# power.net
KiCad netlist of a schematic drawn in Altium Designer
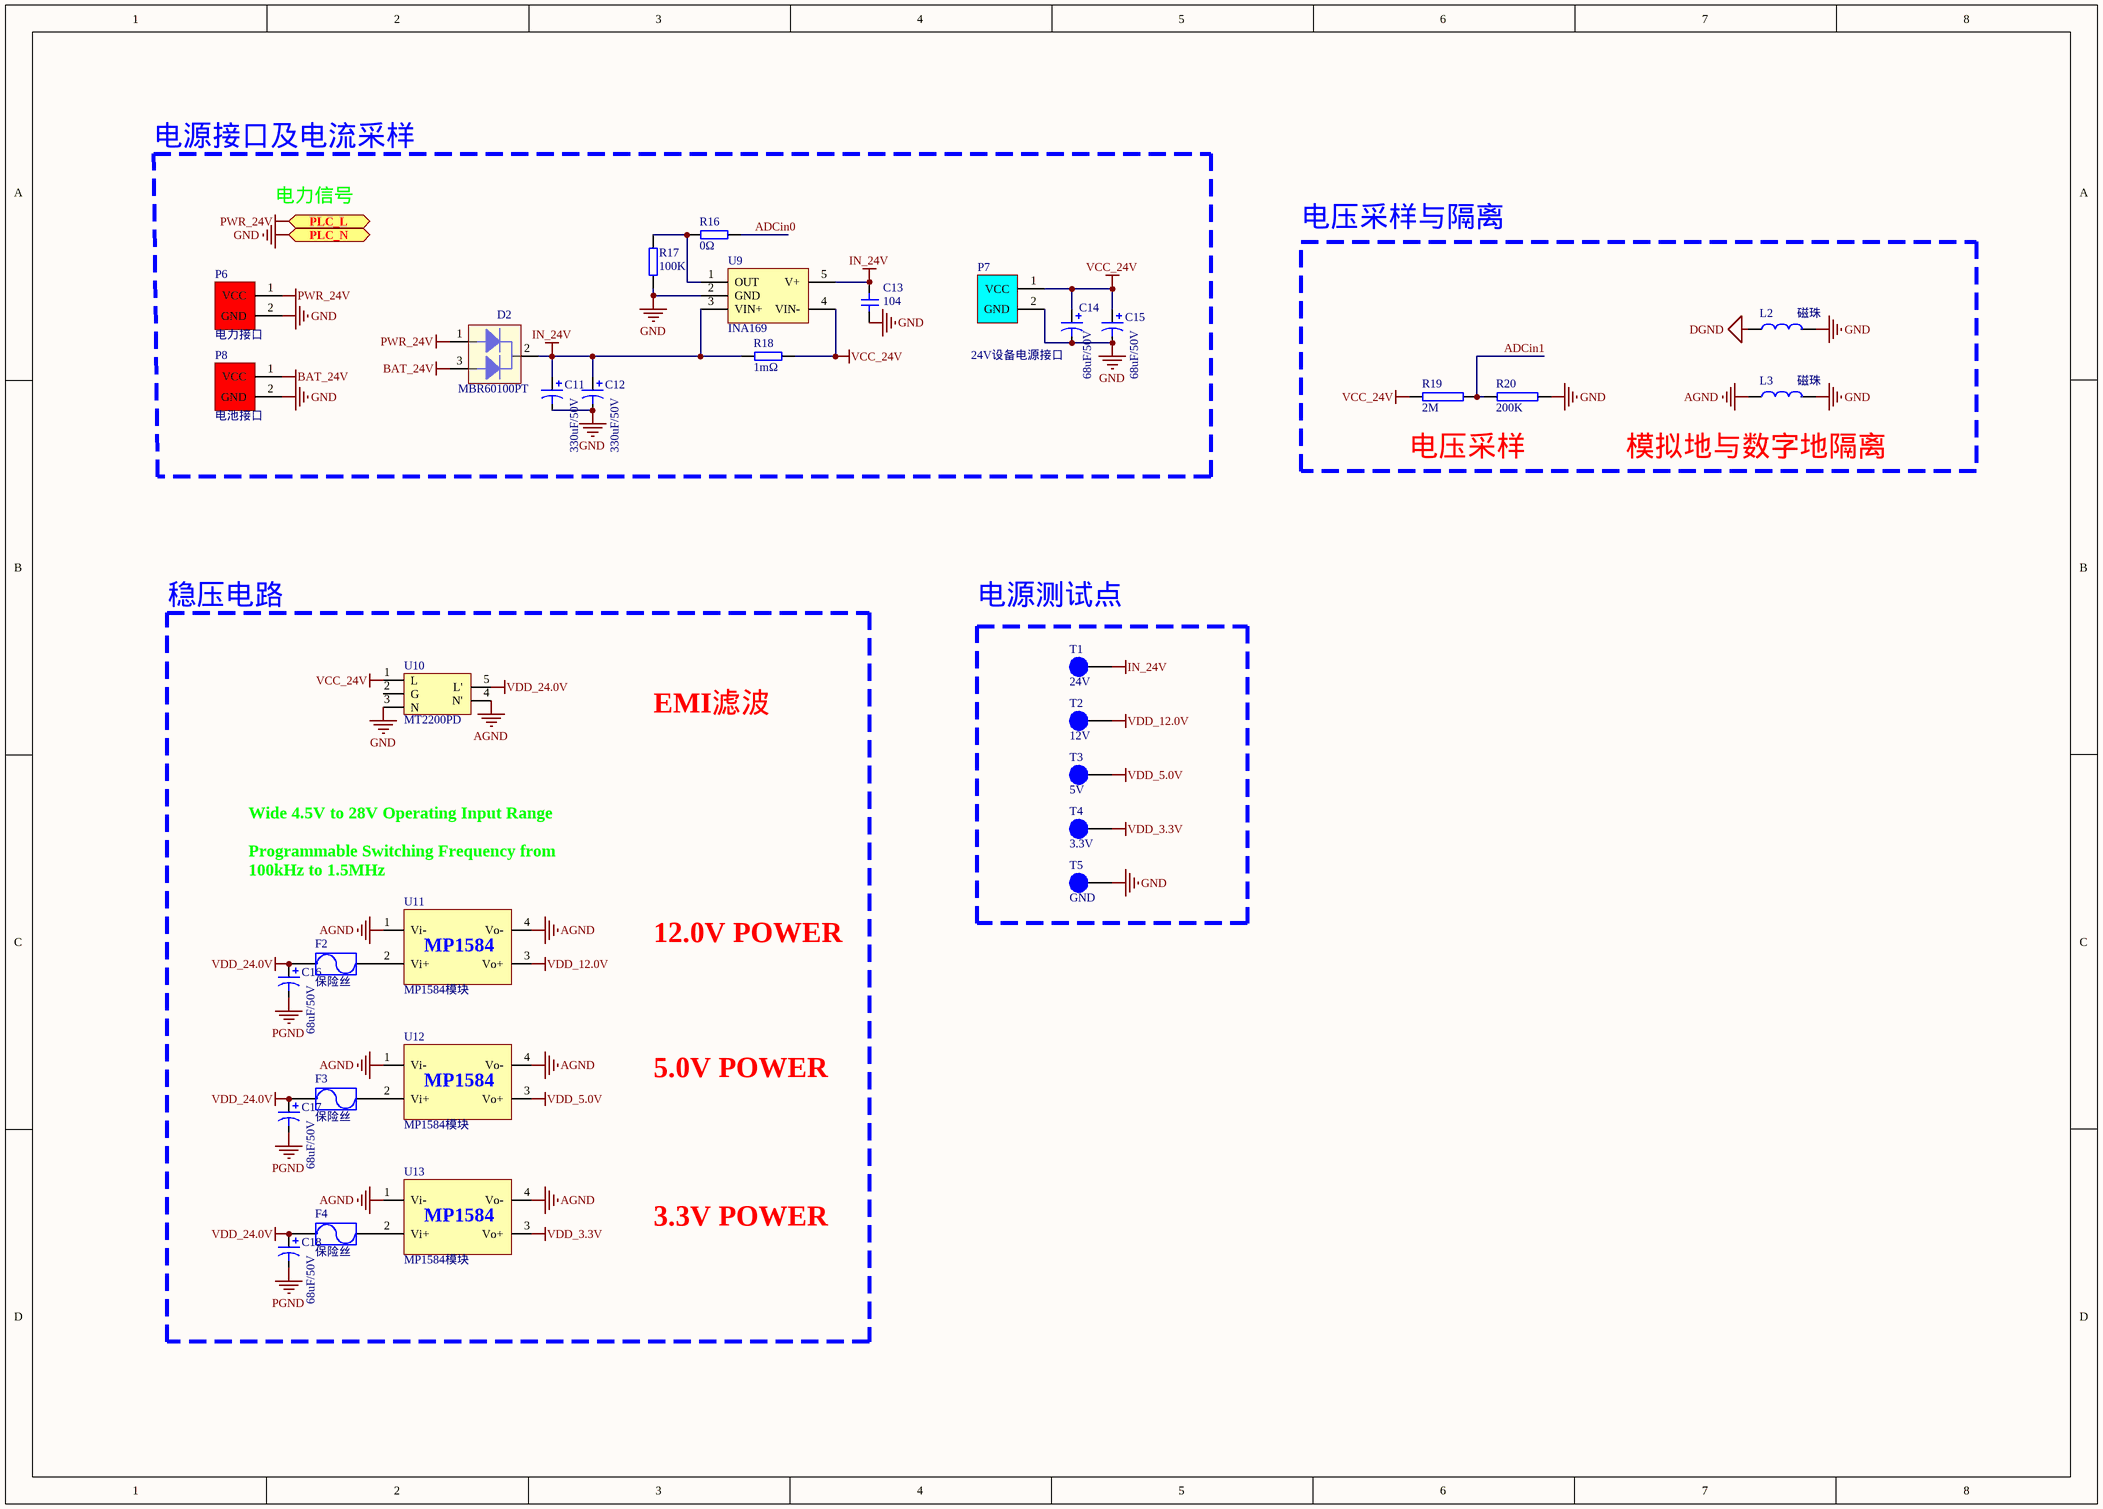
[diagram p0: power.SchDoc]

(export (version "E")
  (design (tool "Eeschema 10.0.6"))
  (components
    (comp (ref "C11")
      (value "330uF/50V")
      (footprint "RB.2.4")
      (description "直插极性电容")
      (libsource (lib "集大电协1.5") (part "Cap3"))
    )
    (comp (ref "C12")
      (value "330uF/50V")
      (footprint "RB.2.4")
      (description "直插极性电容")
      (libsource (lib "集大电协1.5") (part "Cap3"))
    )
    (comp (ref "C13")
      (value "104")
      (footprint "0805C")
      (description "无极贴片电容")
      (libsource (lib "集大电协1.5") (part "Cap1"))
    )
    (comp (ref "C14")
      (value "68uF/50V")
      (footprint "RB.1.2")
      (description "直插极性电容")
      (libsource (lib "集大电协1.5") (part "Cap3"))
    )
    (comp (ref "C15")
      (value "68uF/50V")
      (footprint "RB.1.2")
      (description "直插极性电容")
      (libsource (lib "集大电协1.5") (part "Cap3"))
    )
    (comp (ref "C16")
      (value "68uF/50V")
      (footprint "RB.1.2")
      (description "直插极性电容")
      (libsource (lib "集大电协1.5") (part "Cap3"))
    )
    (comp (ref "C17")
      (value "68uF/50V")
      (footprint "RB.1.2")
      (description "直插极性电容")
      (libsource (lib "集大电协1.5") (part "Cap3"))
    )
    (comp (ref "C18")
      (value "68uF/50V")
      (footprint "RB.1.2")
      (description "直插极性电容")
      (libsource (lib "集大电协1.5") (part "Cap3"))
    )
    (comp (ref "D2")
      (value "MBR60100PT")
      (footprint "TO-247LS")
      (libsource (lib "集大电协1.5") (part "MBR60100PT"))
    )
    (comp (ref "F2") (value "保险丝") (footprint "FUSE-1812") (libsource (lib "集大电协1.5") (part "Fuse")))
    (comp (ref "F3") (value "保险丝") (footprint "FUSE-1812") (libsource (lib "集大电协1.5") (part "Fuse")))
    (comp (ref "F4") (value "保险丝") (footprint "FUSE-1812") (libsource (lib "集大电协1.5") (part "Fuse")))
    (comp (ref "L2")
      (value "磁珠")
      (footprint "1206L")
      (description "电感")
      (libsource (lib "集大电协1.5") (part "L"))
    )
    (comp (ref "L3")
      (value "磁珠")
      (footprint "1206L")
      (description "电感")
      (libsource (lib "集大电协1.5") (part "L"))
    )
    (comp (ref "P6") (value "电力接口") (footprint "XT60-F") (libsource (lib "集大电协1.5") (part "电源端子")))
    (comp (ref "P7") (value "24V设备电源接口") (footprint "XT60-F") (libsource (lib "集大电协1.5") (part "推进器电源")))
    (comp (ref "P8") (value "电池接口") (footprint "XT60-F") (libsource (lib "集大电协1.5") (part "电源端子")))
    (comp (ref "R16")
      (value "0Ω")
      (footprint "0805R")
      (description "电阻")
      (libsource (lib "集大电协1.5") (part "Res"))
    )
    (comp (ref "R17")
      (value "100K")
      (footprint "0805R")
      (description "电阻")
      (libsource (lib "集大电协1.5") (part "Res"))
    )
    (comp (ref "R18")
      (value "1mΩ")
      (footprint "2512R")
      (description "电阻")
      (libsource (lib "集大电协1.5") (part "Res"))
    )
    (comp (ref "R19") (value "2M") (footprint "0805R") (libsource (lib "窝牛器件封装") (part "R1")))
    (comp (ref "R20") (value "200K") (footprint "0805R") (libsource (lib "窝牛器件封装") (part "R1")))
    (comp (ref "T1")
      (value "24V")
      (footprint "HEADER 1")
      (description "测试点")
      (libsource (lib "集大电协1.2") (part "测试点"))
    )
    (comp (ref "T2")
      (value "12V")
      (footprint "HEADER 1")
      (description "测试点")
      (libsource (lib "集大电协1.2") (part "测试点"))
    )
    (comp (ref "T3")
      (value "5V")
      (footprint "HEADER 1")
      (description "测试点")
      (libsource (lib "集大电协1.2") (part "测试点"))
    )
    (comp (ref "T4")
      (value "3.3V")
      (footprint "HEADER 1")
      (description "测试点")
      (libsource (lib "集大电协1.2") (part "测试点"))
    )
    (comp (ref "T5")
      (value "GND")
      (footprint "HEADER 1")
      (description "测试点")
      (libsource (lib "集大电协1.2") (part "测试点"))
    )
    (comp (ref "U9") (value "INA169") (footprint "SOT23-5") (libsource (lib "集大电协1.5") (part "INA169")))
    (comp (ref "U10")
      (value "MT2200PD")
      (footprint "MT2200PD-6A")
      (libsource (lib "集大电协1.5") (part "MT2200PD"))
    )
    (comp (ref "U11")
      (value "MP1584模块")
      (footprint "MP1584电源模块")
      (libsource (lib "集大电协1.5") (part "MP1584电源模块"))
    )
    (comp (ref "U12")
      (value "MP1584模块")
      (footprint "MP1584电源模块")
      (libsource (lib "集大电协1.5") (part "MP1584电源模块"))
    )
    (comp (ref "U13")
      (value "MP1584模块")
      (footprint "MP1584电源模块")
      (libsource (lib "集大电协1.5") (part "MP1584电源模块"))
    )
  )
  (nets
    (net (code "2") (name "/ADCin0") (class "Default")
      (node (ref "R16") (pin "1") (pinfunction "1_1") (pintype "passive"))
    )
    (net (code "3") (name "/ADCin1") (class "Default")
      (node (ref "R19") (pin "2") (pinfunction "2_2") (pintype "passive"))
      (node (ref "R20") (pin "1") (pinfunction "1_1") (pintype "passive"))
    )
    (net (code "4") (name "AGND") (class "Default")
      (node (ref "L3") (pin "1") (pinfunction "1_1") (pintype "passive"))
      (node (ref "U10") (pin "4") (pinfunction "N'_4") (pintype "passive"))
      (node (ref "U11") (pin "1") (pinfunction "Vi-_1") (pintype "passive"))
      (node (ref "U11") (pin "4") (pinfunction "Vo-_4") (pintype "passive"))
      (node (ref "U12") (pin "1") (pinfunction "Vi-_1") (pintype "passive"))
      (node (ref "U12") (pin "4") (pinfunction "Vo-_4") (pintype "passive"))
      (node (ref "U13") (pin "1") (pinfunction "Vi-_1") (pintype "passive"))
      (node (ref "U13") (pin "4") (pinfunction "Vo-_4") (pintype "passive"))
    )
    (net (code "5") (name "BAT_24V") (class "Default")
      (node (ref "D2") (pin "3") (pintype "passive"))
      (node (ref "P8") (pin "1") (pinfunction "VCC_1") (pintype "passive"))
    )
    (net (code "6") (name "DGND") (class "Default")
      (node (ref "L2") (pin "1") (pinfunction "1_1") (pintype "passive"))
    )
    (net (code "7") (name "GND") (class "Default")
      (node (ref "C11") (pin "2") (pinfunction "2_2") (pintype "passive"))
      (node (ref "C12") (pin "2") (pinfunction "2_2") (pintype "passive"))
      (node (ref "C13") (pin "1") (pinfunction "1_1") (pintype "passive"))
      (node (ref "C14") (pin "2") (pinfunction "2_2") (pintype "passive"))
      (node (ref "C15") (pin "2") (pinfunction "2_2") (pintype "passive"))
      (node (ref "L2") (pin "2") (pinfunction "2_2") (pintype "passive"))
      (node (ref "L3") (pin "2") (pinfunction "2_2") (pintype "passive"))
      (node (ref "P6") (pin "2") (pinfunction "GND_2") (pintype "passive"))
      (node (ref "P7") (pin "2") (pinfunction "GND_2") (pintype "passive"))
      (node (ref "P8") (pin "2") (pinfunction "GND_2") (pintype "passive"))
      (node (ref "R17") (pin "1") (pinfunction "1_1") (pintype "passive"))
      (node (ref "R20") (pin "2") (pinfunction "2_2") (pintype "passive"))
      (node (ref "T5") (pin "1") (pinfunction "1_1") (pintype "passive"))
      (node (ref "U10") (pin "3") (pinfunction "N_3") (pintype "passive"))
      (node (ref "U9") (pin "2") (pinfunction "GND_2") (pintype "passive"))
    )
    (net (code "8") (name "IN_24V") (class "Default")
      (node (ref "C11") (pin "1") (pinfunction "1_1") (pintype "passive"))
      (node (ref "C12") (pin "1") (pinfunction "1_1") (pintype "passive"))
      (node (ref "C13") (pin "2") (pinfunction "2_2") (pintype "passive"))
      (node (ref "D2") (pin "2") (pinfunction "2_2") (pintype "passive"))
      (node (ref "R18") (pin "2") (pinfunction "2_2") (pintype "passive"))
      (node (ref "T1") (pin "1") (pinfunction "1_1") (pintype "passive"))
      (node (ref "U9") (pin "3") (pinfunction "VIN+_3") (pintype "passive"))
      (node (ref "U9") (pin "5") (pinfunction "V+_5") (pintype "passive"))
    )
    (net (code "9") (name "Net-(U9-OUT)") (class "Default")
      (node (ref "R16") (pin "2") (pinfunction "2_2") (pintype "passive"))
      (node (ref "R17") (pin "2") (pinfunction "2_2") (pintype "passive"))
      (node (ref "U9") (pin "1") (pinfunction "OUT_1") (pintype "passive"))
    )
    (net (code "10") (name "Net-(U11-Vi+)") (class "Default")
      (node (ref "F2") (pin "2") (pinfunction "2_2") (pintype "passive"))
      (node (ref "U11") (pin "2") (pinfunction "Vi+_2") (pintype "passive"))
    )
    (net (code "11") (name "Net-(U12-Vi+)") (class "Default")
      (node (ref "F3") (pin "2") (pinfunction "2_2") (pintype "passive"))
      (node (ref "U12") (pin "2") (pinfunction "Vi+_2") (pintype "passive"))
    )
    (net (code "12") (name "Net-(U13-Vi+)") (class "Default")
      (node (ref "F4") (pin "2") (pinfunction "2_2") (pintype "passive"))
      (node (ref "U13") (pin "2") (pinfunction "Vi+_2") (pintype "passive"))
    )
    (net (code "13") (name "PGND") (class "Default")
      (node (ref "C16") (pin "2") (pinfunction "2_2") (pintype "passive"))
      (node (ref "C17") (pin "2") (pinfunction "2_2") (pintype "passive"))
      (node (ref "C18") (pin "2") (pinfunction "2_2") (pintype "passive"))
    )
    (net (code "14") (name "PWR_24V") (class "Default")
      (node (ref "D2") (pin "1") (pintype "passive"))
      (node (ref "P6") (pin "1") (pinfunction "VCC_1") (pintype "passive"))
    )
    (net (code "15") (name "VCC_24V") (class "Default")
      (node (ref "C14") (pin "1") (pinfunction "1_1") (pintype "passive"))
      (node (ref "C15") (pin "1") (pinfunction "1_1") (pintype "passive"))
      (node (ref "P7") (pin "1") (pinfunction "VCC_1") (pintype "passive"))
      (node (ref "R18") (pin "1") (pinfunction "1_1") (pintype "passive"))
      (node (ref "R19") (pin "1") (pinfunction "1_1") (pintype "passive"))
      (node (ref "U10") (pin "1") (pinfunction "L_1") (pintype "passive"))
      (node (ref "U9") (pin "4") (pinfunction "VIN-_4") (pintype "passive"))
    )
    (net (code "16") (name "VDD_3.3V") (class "Default")
      (node (ref "T4") (pin "1") (pinfunction "1_1") (pintype "passive"))
      (node (ref "U13") (pin "3") (pinfunction "Vo+_3") (pintype "passive"))
    )
    (net (code "17") (name "VDD_5.0V") (class "Default")
      (node (ref "T3") (pin "1") (pinfunction "1_1") (pintype "passive"))
      (node (ref "U12") (pin "3") (pinfunction "Vo+_3") (pintype "passive"))
    )
    (net (code "18") (name "VDD_12.0V") (class "Default")
      (node (ref "T2") (pin "1") (pinfunction "1_1") (pintype "passive"))
      (node (ref "U11") (pin "3") (pinfunction "Vo+_3") (pintype "passive"))
    )
    (net (code "19") (name "VDD_24.0V") (class "Default")
      (node (ref "C16") (pin "1") (pinfunction "1_1") (pintype "passive"))
      (node (ref "C17") (pin "1") (pinfunction "1_1") (pintype "passive"))
      (node (ref "C18") (pin "1") (pinfunction "1_1") (pintype "passive"))
      (node (ref "F2") (pin "1") (pinfunction "1_1") (pintype "passive"))
      (node (ref "F3") (pin "1") (pinfunction "1_1") (pintype "passive"))
      (node (ref "F4") (pin "1") (pinfunction "1_1") (pintype "passive"))
      (node (ref "U10") (pin "5") (pinfunction "L'_5") (pintype "passive"))
    )
    (net (code "20") (name "unconnected-(U10-G-Pad2)") (class "Default")
      (node (ref "U10") (pin "2") (pinfunction "G_2") (pintype "passive"))
    )
  )
)
